# Isolator2_0.net
KiCad netlist of a schematic drawn in EAGLE
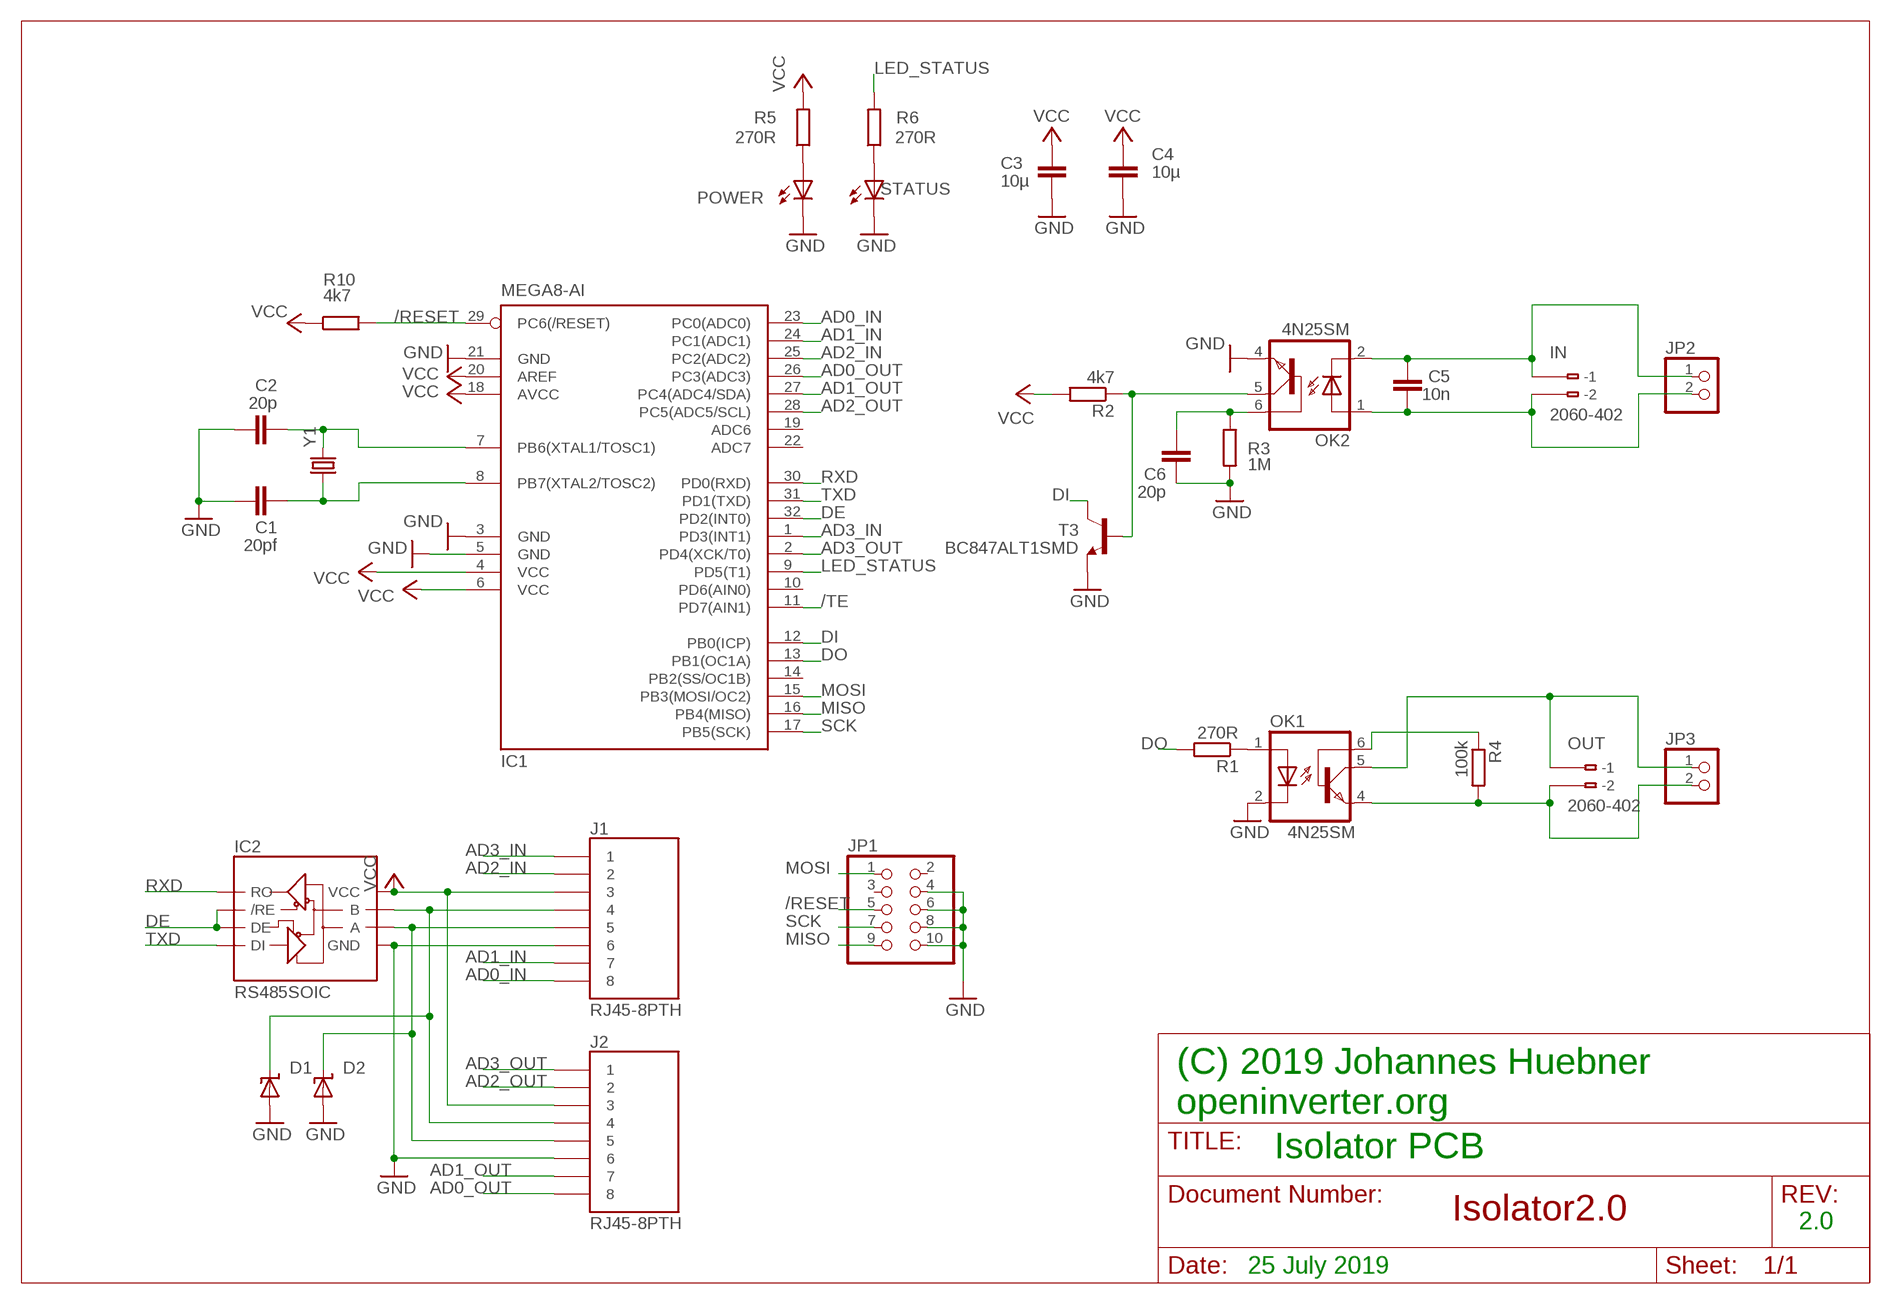
[diagram p0: schematic, sheet 1]

(export (version "E")
  (design (tool "Eeschema 10.0.6"))
  (components
    (comp (ref "C1")
      (value "20pf")
      (footprint "eagle-import:C0805")
      (libsource (lib "eagle-import") (part "C-EUC0805"))
    )
    (comp (ref "C2")
      (value "20p")
      (footprint "eagle-import:C0805")
      (libsource (lib "eagle-import") (part "C-EUC0805"))
    )
    (comp (ref "C3")
      (value "10µ")
      (footprint "eagle-import:C0805")
      (libsource (lib "eagle-import") (part "C-EUC0805"))
    )
    (comp (ref "C4")
      (value "10µ")
      (footprint "eagle-import:C0805")
      (libsource (lib "eagle-import") (part "C-EUC0805"))
    )
    (comp (ref "C5")
      (value "10n")
      (footprint "eagle-import:C0805")
      (libsource (lib "eagle-import") (part "C-EUC0805"))
    )
    (comp (ref "C6")
      (value "20p")
      (footprint "eagle-import:C0805")
      (libsource (lib "eagle-import") (part "C-EUC0805"))
    )
    (comp (ref "D1")
      (value "SUPPRESSOR-SMBJ")
      (footprint "eagle-import:SMBJ")
      (libsource (lib "eagle-import") (part "SUPPRESSOR-SMBJ"))
    )
    (comp (ref "D2")
      (value "SUPPRESSOR-SMBJ")
      (footprint "eagle-import:SMBJ")
      (libsource (lib "eagle-import") (part "SUPPRESSOR-SMBJ"))
    )
    (comp (ref "IC1")
      (value "MEGA8-AI")
      (footprint "eagle-import:TQFP32-08")
      (fields (field (name "MPN") "ATMEGA8-16AU"))
      (libsource (lib "eagle-import") (part "MEGA8-AI"))
    )
    (comp (ref "IC2")
      (value "RS485SOIC")
      (footprint "eagle-import:SO08")
      (libsource (lib "eagle-import") (part "RS485SOIC"))
    )
    (comp (ref "IN")
      (value "2060-402")
      (footprint "eagle-import:2060-402")
      (libsource (lib "eagle-import") (part "2060-402"))
    )
    (comp (ref "J1")
      (value "RJ45-8PTH")
      (footprint "eagle-import:RJ45-8")
      (libsource (lib "eagle-import") (part "RJ45-8PTH"))
    )
    (comp (ref "J2")
      (value "RJ45-8PTH")
      (footprint "eagle-import:RJ45-8")
      (libsource (lib "eagle-import") (part "RJ45-8PTH"))
    )
    (comp (ref "JP1")
      (value "PINHD-2X5")
      (footprint "eagle-import:2X05")
      (libsource (lib "eagle-import") (part "PINHD-2X5"))
    )
    (comp (ref "JP2")
      (value "PINHD-1X2")
      (footprint "eagle-import:1X02")
      (libsource (lib "eagle-import") (part "PINHD-1X2"))
    )
    (comp (ref "JP3")
      (value "PINHD-1X2")
      (footprint "eagle-import:1X02")
      (libsource (lib "eagle-import") (part "PINHD-1X2"))
    )
    (comp (ref "OK1")
      (value "4N25SM")
      (footprint "eagle-import:DIL6-SMD")
      (fields (field (name "MF") "FAIRCHILD SEMICONDUCTOR"))
      (libsource (lib "eagle-import") (part "4N?MS25"))
    )
    (comp (ref "OK2")
      (value "4N25SM")
      (footprint "eagle-import:DIL6-SMD")
      (fields (field (name "MF") "FAIRCHILD SEMICONDUCTOR"))
      (libsource (lib "eagle-import") (part "4N?MS25"))
    )
    (comp (ref "OUT")
      (value "2060-402")
      (footprint "eagle-import:2060-402")
      (libsource (lib "eagle-import") (part "2060-402"))
    )
    (comp (ref "POWER")
      (value "LEDCHIP-LED0805")
      (footprint "eagle-import:CHIP-LED0805")
      (libsource (lib "eagle-import") (part "LEDCHIP-LED0805"))
    )
    (comp (ref "R1")
      (value "270R")
      (footprint "eagle-import:M0805")
      (libsource (lib "eagle-import") (part "R-EU_M0805"))
    )
    (comp (ref "R2")
      (value "4k7")
      (footprint "eagle-import:M0805")
      (libsource (lib "eagle-import") (part "R-EU_M0805"))
    )
    (comp (ref "R3")
      (value "1M")
      (footprint "eagle-import:M0805")
      (libsource (lib "eagle-import") (part "R-EU_M0805"))
    )
    (comp (ref "R4")
      (value "100k")
      (footprint "eagle-import:M0805")
      (libsource (lib "eagle-import") (part "R-EU_M0805"))
    )
    (comp (ref "R5")
      (value "270R")
      (footprint "eagle-import:M0805")
      (libsource (lib "eagle-import") (part "R-EU_M0805"))
    )
    (comp (ref "R6")
      (value "270R")
      (footprint "eagle-import:M0805")
      (libsource (lib "eagle-import") (part "R-EU_M0805"))
    )
    (comp (ref "R10")
      (value "4k7")
      (footprint "eagle-import:M0805")
      (libsource (lib "eagle-import") (part "R-EU_M0805"))
    )
    (comp (ref "STATUS")
      (value "LEDCHIP-LED0805")
      (footprint "eagle-import:CHIP-LED0805")
      (libsource (lib "eagle-import") (part "LEDCHIP-LED0805"))
    )
    (comp (ref "T3")
      (value "BC847ALT1SMD")
      (footprint "eagle-import:SOT23")
      (libsource (lib "eagle-import") (part "BC847SMDALT1"))
    )
    (comp (ref "Y1")
      (value "CRYSTAL10.5X4.8")
      (footprint "eagle-import:CRYSTAL-SMD-10.5X4.8-2PIN")
      (libsource (lib "eagle-import") (part "CRYSTAL10.5X4.8"))
    )
  )
  (nets
    (net (code "1") (name "/AD0_IN") (class "Default")
      (node (ref "IC1") (pin "23") (pinfunction "PC0(ADC0)_23") (pintype "bidirectional"))
      (node (ref "J1") (pin "8") (pinfunction "8_8") (pintype "bidirectional"))
    )
    (net (code "2") (name "/AD0_OUT") (class "Default")
      (node (ref "IC1") (pin "26") (pinfunction "PC3(ADC3)_26") (pintype "bidirectional"))
      (node (ref "J2") (pin "8") (pinfunction "8_8") (pintype "bidirectional"))
    )
    (net (code "3") (name "/AD1_IN") (class "Default")
      (node (ref "IC1") (pin "24") (pinfunction "PC1(ADC1)_24") (pintype "bidirectional"))
      (node (ref "J1") (pin "7") (pinfunction "7_7") (pintype "bidirectional"))
    )
    (net (code "4") (name "/AD1_OUT") (class "Default")
      (node (ref "IC1") (pin "27") (pinfunction "PC4(ADC4/SDA)_27") (pintype "bidirectional"))
      (node (ref "J2") (pin "7") (pinfunction "7_7") (pintype "bidirectional"))
    )
    (net (code "5") (name "/AD2_IN") (class "Default")
      (node (ref "IC1") (pin "25") (pinfunction "PC2(ADC2)_25") (pintype "bidirectional"))
      (node (ref "J1") (pin "2") (pinfunction "2_2") (pintype "bidirectional"))
    )
    (net (code "6") (name "/AD2_OUT") (class "Default")
      (node (ref "IC1") (pin "28") (pinfunction "PC5(ADC5/SCL)_28") (pintype "bidirectional"))
      (node (ref "J2") (pin "2") (pinfunction "2_2") (pintype "bidirectional"))
    )
    (net (code "7") (name "/AD3_IN") (class "Default")
      (node (ref "IC1") (pin "1") (pinfunction "PD3(INT1)_1") (pintype "bidirectional"))
      (node (ref "J1") (pin "1") (pinfunction "1_1") (pintype "bidirectional"))
    )
    (net (code "8") (name "/AD3_OUT") (class "Default")
      (node (ref "IC1") (pin "2") (pinfunction "PD4(XCK/T0)_2") (pintype "bidirectional"))
      (node (ref "J2") (pin "1") (pinfunction "1_1") (pintype "bidirectional"))
    )
    (net (code "9") (name "/DE") (class "Default")
      (node (ref "IC1") (pin "32") (pinfunction "PD2(INT0)_32") (pintype "bidirectional"))
      (node (ref "IC2") (pin "2") (pinfunction "/RE_2") (pintype "bidirectional"))
      (node (ref "IC2") (pin "3") (pinfunction "DE_3") (pintype "bidirectional"))
    )
    (net (code "10") (name "/DI") (class "Default")
      (node (ref "IC1") (pin "12") (pinfunction "PB0(ICP)_12") (pintype "bidirectional"))
      (node (ref "T3") (pin "3") (pinfunction "C_3") (pintype "passive"))
    )
    (net (code "11") (name "/DO") (class "Default")
      (node (ref "IC1") (pin "13") (pinfunction "PB1(OC1A)_13") (pintype "bidirectional"))
      (node (ref "R1") (pin "2") (pinfunction "2_2") (pintype "passive"))
    )
    (net (code "12") (name "/LED_STATUS") (class "Default")
      (node (ref "IC1") (pin "9") (pinfunction "PD5(T1)_9") (pintype "bidirectional"))
      (node (ref "R6") (pin "2") (pinfunction "2_2") (pintype "passive"))
    )
    (net (code "13") (name "/MISO") (class "Default")
      (node (ref "IC1") (pin "16") (pinfunction "PB4(MISO)_16") (pintype "bidirectional"))
      (node (ref "JP1") (pin "9") (pinfunction "9_9") (pintype "passive"))
    )
    (net (code "14") (name "/MOSI") (class "Default")
      (node (ref "IC1") (pin "15") (pinfunction "PB3(MOSI/OC2)_15") (pintype "bidirectional"))
      (node (ref "JP1") (pin "1") (pinfunction "1_1") (pintype "passive"))
    )
    (net (code "15") (name "/RXD") (class "Default")
      (node (ref "IC1") (pin "30") (pinfunction "PD0(RXD)_30") (pintype "bidirectional"))
      (node (ref "IC2") (pin "1") (pinfunction "RO_1") (pintype "bidirectional"))
    )
    (net (code "16") (name "/SCK") (class "Default")
      (node (ref "IC1") (pin "17") (pinfunction "PB5(SCK)_17") (pintype "bidirectional"))
      (node (ref "JP1") (pin "7") (pinfunction "7_7") (pintype "passive"))
    )
    (net (code "17") (name "/TXD") (class "Default")
      (node (ref "IC1") (pin "31") (pinfunction "PD1(TXD)_31") (pintype "bidirectional"))
      (node (ref "IC2") (pin "4") (pinfunction "DI_4") (pintype "bidirectional"))
    )
    (net (code "18") (name "/{slash}RESET") (class "Default")
      (node (ref "IC1") (pin "29") (pinfunction "PC6(/RESET)_29") (pintype "bidirectional"))
      (node (ref "JP1") (pin "5") (pinfunction "5_5") (pintype "passive"))
      (node (ref "R10") (pin "2") (pinfunction "2_2") (pintype "passive"))
    )
    (net (code "19") (name "/{slash}TE") (class "Default")
      (node (ref "IC1") (pin "11") (pinfunction "PD7(AIN1)_11") (pintype "bidirectional"))
    )
    (net (code "20") (name "GND") (class "Default")
      (node (ref "C1") (pin "1") (pinfunction "1_1") (pintype "passive"))
      (node (ref "C2") (pin "1") (pinfunction "1_1") (pintype "passive"))
      (node (ref "C3") (pin "2") (pinfunction "2_2") (pintype "passive"))
      (node (ref "C4") (pin "2") (pinfunction "2_2") (pintype "passive"))
      (node (ref "C6") (pin "1") (pinfunction "1_1") (pintype "passive"))
      (node (ref "D1") (pin "A") (pinfunction "A_A") (pintype "passive"))
      (node (ref "D2") (pin "A") (pinfunction "A_A") (pintype "passive"))
      (node (ref "IC1") (pin "21") (pinfunction "GND_21") (pintype "power_in"))
      (node (ref "IC1") (pin "3") (pinfunction "GND_3") (pintype "power_in"))
      (node (ref "IC1") (pin "5") (pinfunction "GND_5") (pintype "power_in"))
      (node (ref "IC2") (pin "5") (pinfunction "GND_5") (pintype "bidirectional"))
      (node (ref "J1") (pin "6") (pinfunction "6_6") (pintype "bidirectional"))
      (node (ref "J2") (pin "6") (pinfunction "6_6") (pintype "bidirectional"))
      (node (ref "JP1") (pin "10") (pinfunction "10_10") (pintype "passive"))
      (node (ref "JP1") (pin "4") (pinfunction "4_4") (pintype "passive"))
      (node (ref "JP1") (pin "6") (pinfunction "6_6") (pintype "passive"))
      (node (ref "JP1") (pin "8") (pinfunction "8_8") (pintype "passive"))
      (node (ref "OK1") (pin "2") (pinfunction "C_2") (pintype "passive"))
      (node (ref "OK2") (pin "4") (pinfunction "EMI_4") (pintype "passive"))
      (node (ref "POWER") (pin "C") (pinfunction "C_C") (pintype "passive"))
      (node (ref "R3") (pin "2") (pinfunction "2_2") (pintype "passive"))
      (node (ref "STATUS") (pin "C") (pinfunction "C_C") (pintype "passive"))
      (node (ref "T3") (pin "2") (pinfunction "E_2") (pintype "passive"))
    )
    (net (code "21") (name "Net-(IC1-PB6(XTAL1{slash}TOSC1))") (class "Default")
      (node (ref "C2") (pin "2") (pinfunction "2_2") (pintype "passive"))
      (node (ref "IC1") (pin "7") (pinfunction "PB6(XTAL1/TOSC1)_7") (pintype "bidirectional"))
      (node (ref "Y1") (pin "P$2") (pinfunction "2_P$2") (pintype "passive"))
    )
    (net (code "22") (name "Net-(IC1-PB7(XTAL2{slash}TOSC2))") (class "Default")
      (node (ref "C1") (pin "2") (pinfunction "2_2") (pintype "passive"))
      (node (ref "IC1") (pin "8") (pinfunction "PB7(XTAL2/TOSC2)_8") (pintype "bidirectional"))
      (node (ref "Y1") (pin "P$1") (pinfunction "1_P$1") (pintype "passive"))
    )
    (net (code "23") (name "Net-(IC2-A)") (class "Default")
      (node (ref "D2") (pin "C") (pinfunction "C_C") (pintype "passive"))
      (node (ref "IC2") (pin "6") (pinfunction "A_6") (pintype "bidirectional"))
      (node (ref "J1") (pin "5") (pinfunction "5_5") (pintype "bidirectional"))
      (node (ref "J2") (pin "5") (pinfunction "5_5") (pintype "bidirectional"))
    )
    (net (code "24") (name "Net-(IC2-B)") (class "Default")
      (node (ref "D1") (pin "C") (pinfunction "C_C") (pintype "passive"))
      (node (ref "IC2") (pin "7") (pinfunction "B_7") (pintype "bidirectional"))
      (node (ref "J1") (pin "4") (pinfunction "4_4") (pintype "bidirectional"))
      (node (ref "J2") (pin "4") (pinfunction "4_4") (pintype "bidirectional"))
    )
    (net (code "25") (name "Net-(IN-B-1)") (class "Default")
      (node (ref "C5") (pin "2") (pinfunction "2_2") (pintype "passive"))
      (node (ref "IN") (pin "P21") (pinfunction "B-1_P21") (pintype "passive"))
      (node (ref "JP2") (pin "1") (pinfunction "1_1") (pintype "passive"))
      (node (ref "OK2") (pin "2") (pinfunction "C_2") (pintype "passive"))
    )
    (net (code "26") (name "Net-(IN-B-2)") (class "Default")
      (node (ref "C5") (pin "1") (pinfunction "1_1") (pintype "passive"))
      (node (ref "IN") (pin "P22") (pinfunction "B-2_P22") (pintype "passive"))
      (node (ref "JP2") (pin "2") (pinfunction "2_2") (pintype "passive"))
      (node (ref "OK2") (pin "1") (pinfunction "A_1") (pintype "passive"))
    )
    (net (code "27") (name "Net-(OK1-A)") (class "Default")
      (node (ref "OK1") (pin "1") (pinfunction "A_1") (pintype "passive"))
      (node (ref "R1") (pin "1") (pinfunction "1_1") (pintype "passive"))
    )
    (net (code "28") (name "Net-(OK1-BAS)") (class "Default")
      (node (ref "OK1") (pin "6") (pinfunction "BAS_6") (pintype "passive"))
      (node (ref "R4") (pin "1") (pinfunction "1_1") (pintype "passive"))
    )
    (net (code "29") (name "Net-(OK1-COL)") (class "Default")
      (node (ref "JP3") (pin "1") (pinfunction "1_1") (pintype "passive"))
      (node (ref "OK1") (pin "5") (pinfunction "COL_5") (pintype "passive"))
      (node (ref "OUT") (pin "P21") (pinfunction "B-1_P21") (pintype "passive"))
    )
    (net (code "30") (name "Net-(OK1-EMI)") (class "Default")
      (node (ref "JP3") (pin "2") (pinfunction "2_2") (pintype "passive"))
      (node (ref "OK1") (pin "4") (pinfunction "EMI_4") (pintype "passive"))
      (node (ref "OUT") (pin "P22") (pinfunction "B-2_P22") (pintype "passive"))
      (node (ref "R4") (pin "2") (pinfunction "2_2") (pintype "passive"))
    )
    (net (code "31") (name "Net-(OK2-BAS)") (class "Default")
      (node (ref "C6") (pin "2") (pinfunction "2_2") (pintype "passive"))
      (node (ref "OK2") (pin "6") (pinfunction "BAS_6") (pintype "passive"))
      (node (ref "R3") (pin "1") (pinfunction "1_1") (pintype "passive"))
    )
    (net (code "32") (name "Net-(OK2-COL)") (class "Default")
      (node (ref "OK2") (pin "5") (pinfunction "COL_5") (pintype "passive"))
      (node (ref "R2") (pin "1") (pinfunction "1_1") (pintype "passive"))
      (node (ref "T3") (pin "1") (pinfunction "B_1") (pintype "passive"))
    )
    (net (code "33") (name "Net-(POWER-PadA)") (class "Default")
      (node (ref "POWER") (pin "A") (pinfunction "A_A") (pintype "passive"))
      (node (ref "R5") (pin "1") (pinfunction "1_1") (pintype "passive"))
    )
    (net (code "34") (name "Net-(R6-Pad1)") (class "Default")
      (node (ref "R6") (pin "1") (pinfunction "1_1") (pintype "passive"))
      (node (ref "STATUS") (pin "A") (pinfunction "A_A") (pintype "passive"))
    )
    (net (code "35") (name "VCC") (class "Default")
      (node (ref "C3") (pin "1") (pinfunction "1_1") (pintype "passive"))
      (node (ref "C4") (pin "1") (pinfunction "1_1") (pintype "passive"))
      (node (ref "IC1") (pin "18") (pinfunction "AVCC_18") (pintype "power_in"))
      (node (ref "IC1") (pin "20") (pinfunction "AREF_20") (pintype "passive"))
      (node (ref "IC1") (pin "4") (pinfunction "VCC_4") (pintype "power_in"))
      (node (ref "IC1") (pin "6") (pinfunction "VCC_6") (pintype "power_in"))
      (node (ref "IC2") (pin "8") (pinfunction "VCC_8") (pintype "bidirectional"))
      (node (ref "J1") (pin "3") (pinfunction "3_3") (pintype "bidirectional"))
      (node (ref "J2") (pin "3") (pinfunction "3_3") (pintype "bidirectional"))
      (node (ref "R10") (pin "1") (pinfunction "1_1") (pintype "passive"))
      (node (ref "R2") (pin "2") (pinfunction "2_2") (pintype "passive"))
      (node (ref "R5") (pin "2") (pinfunction "2_2") (pintype "passive"))
    )
    (net (code "36") (name "unconnected-(IC1-ADC6-Pad19)") (class "Default")
      (node (ref "IC1") (pin "19") (pinfunction "ADC6_19") (pintype "bidirectional"))
    )
    (net (code "37") (name "unconnected-(IC1-ADC7-Pad22)") (class "Default")
      (node (ref "IC1") (pin "22") (pinfunction "ADC7_22") (pintype "bidirectional"))
    )
    (net (code "38") (name "unconnected-(IC1-PB2(SS{slash}OC1B)-Pad14)") (class "Default")
      (node (ref "IC1") (pin "14") (pinfunction "PB2(SS/OC1B)_14") (pintype "bidirectional"))
    )
    (net (code "39") (name "unconnected-(IC1-PD6(AIN0)-Pad10)") (class "Default")
      (node (ref "IC1") (pin "10") (pinfunction "PD6(AIN0)_10") (pintype "bidirectional"))
    )
    (net (code "40") (name "unconnected-(IN--1-PadP1.1)") (class "Default")
      (node (ref "IN") (pin "P1.1") (pinfunction "-1_P1.1") (pintype "passive"))
    )
    (net (code "41") (name "unconnected-(IN--2-PadP1.2)") (class "Default")
      (node (ref "IN") (pin "P1.2") (pinfunction "-2_P1.2") (pintype "passive"))
    )
    (net (code "42") (name "unconnected-(JP1-Pad2)") (class "Default")
      (node (ref "JP1") (pin "2") (pinfunction "2_2") (pintype "passive"))
    )
    (net (code "43") (name "unconnected-(JP1-Pad3)") (class "Default")
      (node (ref "JP1") (pin "3") (pinfunction "3_3") (pintype "passive"))
    )
    (net (code "44") (name "unconnected-(OUT--1-PadP1.1)") (class "Default")
      (node (ref "OUT") (pin "P1.1") (pinfunction "-1_P1.1") (pintype "passive"))
    )
    (net (code "45") (name "unconnected-(OUT--2-PadP1.2)") (class "Default")
      (node (ref "OUT") (pin "P1.2") (pinfunction "-2_P1.2") (pintype "passive"))
    )
  )
)
